# esp8266.net
KiCad netlist of a schematic drawn in EAGLE
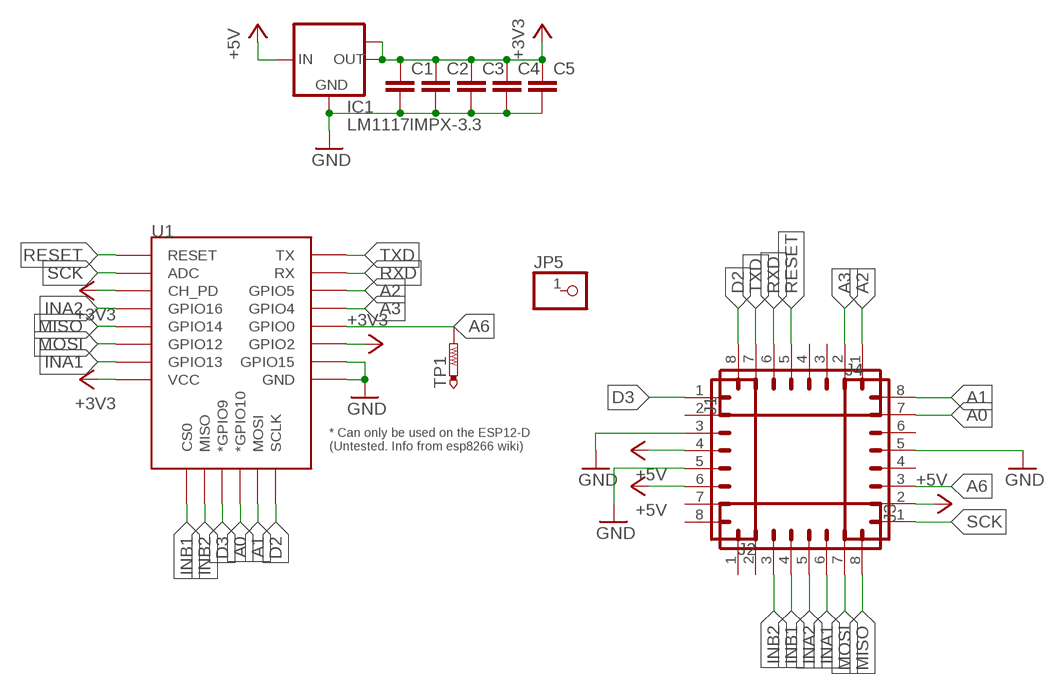
[diagram p0: schematic, sheet 1]

(export (version "E")
  (design (tool "Eeschema 10.0.6"))
  (components
    (comp (ref "C1")
      (value "C-EUC1206K")
      (footprint "eagle-import:C1206K")
      (libsource (lib "eagle-import") (part "C-EUC1206K"))
    )
    (comp (ref "C2")
      (value "C-EUC1206K")
      (footprint "eagle-import:C1206K")
      (libsource (lib "eagle-import") (part "C-EUC1206K"))
    )
    (comp (ref "C3")
      (value "C-EUC1206K")
      (footprint "eagle-import:C1206K")
      (libsource (lib "eagle-import") (part "C-EUC1206K"))
    )
    (comp (ref "C4")
      (value "C-EUC1206K")
      (footprint "eagle-import:C1206K")
      (libsource (lib "eagle-import") (part "C-EUC1206K"))
    )
    (comp (ref "C5")
      (value "C-EUC1206K")
      (footprint "eagle-import:C1206K")
      (libsource (lib "eagle-import") (part "C-EUC1206K"))
    )
    (comp (ref "IC1")
      (value "LM1117IMPX-3.3")
      (footprint "eagle-import:SOT223")
      (libsource (lib "eagle-import") (part "LM1117IMPX-3.3"))
    )
    (comp (ref "J1")
      (value "CONN_08SMD-STRAIGHT-ALT-FEMALE")
      (footprint "eagle-import:1X08_SMD_ALT")
      (libsource (lib "eagle-import") (part "CONN_08SMD-STRAIGHT-ALT-FEMALE"))
    )
    (comp (ref "J2")
      (value "CONN_08SMD-STRAIGHT-ALT-FEMALE")
      (footprint "eagle-import:1X08_SMD_ALT")
      (libsource (lib "eagle-import") (part "CONN_08SMD-STRAIGHT-ALT-FEMALE"))
    )
    (comp (ref "J3")
      (value "CONN_08SMD-STRAIGHT-ALT-FEMALE")
      (footprint "eagle-import:1X08_SMD_ALT")
      (libsource (lib "eagle-import") (part "CONN_08SMD-STRAIGHT-ALT-FEMALE"))
    )
    (comp (ref "J4")
      (value "CONN_08SMD-STRAIGHT-ALT-FEMALE")
      (footprint "eagle-import:1X08_SMD_ALT")
      (libsource (lib "eagle-import") (part "CONN_08SMD-STRAIGHT-ALT-FEMALE"))
    )
    (comp (ref "JP5")
      (value "PINHD-1X1")
      (footprint "eagle-import:1X01")
      (libsource (lib "eagle-import") (part "PINHD-1X1"))
    )
    (comp (ref "TP1")
      (value "PTR1B1,27")
      (footprint "eagle-import:B1,27")
      (libsource (lib "eagle-import") (part "PTR1B1,27"))
    )
    (comp (ref "U1")
      (value "ESP12ESMD")
      (footprint "eagle-import:ESP12E-SMD")
      (libsource (lib "eagle-import") (part "ESP12ESMD"))
    )
  )
  (nets
    (net (code "1") (name "+3V3") (class "Default")
      (node (ref "C1") (pin "1") (pinfunction "1_1") (pintype "passive"))
      (node (ref "C2") (pin "1") (pinfunction "1_1") (pintype "passive"))
      (node (ref "C3") (pin "1") (pinfunction "1_1") (pintype "passive"))
      (node (ref "C4") (pin "1") (pinfunction "1_1") (pintype "passive"))
      (node (ref "C5") (pin "1") (pinfunction "1_1") (pintype "passive"))
      (node (ref "IC1") (pin "2") (pinfunction "OUT_2") (pintype "passive"))
      (node (ref "IC1") (pin "TAB") (pinfunction "OUT1_TAB") (pintype "passive"))
      (node (ref "U1") (pin "CH_PD") (pinfunction "CH_PD_CH_PD") (pintype "bidirectional"))
      (node (ref "U1") (pin "GPIO2") (pinfunction "GPIO2_GPIO2") (pintype "bidirectional"))
      (node (ref "U1") (pin "VCC") (pinfunction "VCC_VCC") (pintype "bidirectional"))
    )
    (net (code "2") (name "+5V") (class "Default")
      (node (ref "IC1") (pin "3") (pinfunction "IN_3") (pintype "input"))
      (node (ref "J2") (pin "4") (pinfunction "4_4") (pintype "passive"))
      (node (ref "J2") (pin "6") (pinfunction "6_6") (pintype "passive"))
      (node (ref "J4") (pin "2") (pinfunction "2_2") (pintype "passive"))
    )
    (net (code "3") (name "A0") (class "Default")
      (node (ref "J4") (pin "7") (pinfunction "7_7") (pintype "passive"))
      (node (ref "U1") (pin "GPIO10") (pinfunction "*GPIO10_GPIO10") (pintype "bidirectional"))
    )
    (net (code "4") (name "A1") (class "Default")
      (node (ref "J4") (pin "8") (pinfunction "8_8") (pintype "passive"))
      (node (ref "U1") (pin "MOSI") (pinfunction "MOSI_MOSI") (pintype "bidirectional"))
    )
    (net (code "5") (name "A2") (class "Default")
      (node (ref "J1") (pin "1") (pinfunction "1_1") (pintype "passive"))
      (node (ref "U1") (pin "GPIO5") (pinfunction "GPIO5_GPIO5") (pintype "bidirectional"))
    )
    (net (code "6") (name "A3") (class "Default")
      (node (ref "J1") (pin "2") (pinfunction "2_2") (pintype "passive"))
      (node (ref "U1") (pin "GPIO4") (pinfunction "GPIO4_GPIO4") (pintype "bidirectional"))
    )
    (net (code "7") (name "A6") (class "Default")
      (node (ref "J4") (pin "3") (pinfunction "3_3") (pintype "passive"))
      (node (ref "TP1") (pin "TP") (pinfunction "TP_TP") (pintype "input"))
      (node (ref "U1") (pin "GPIO0") (pinfunction "GPIO0_GPIO0") (pintype "bidirectional"))
    )
    (net (code "8") (name "D2") (class "Default")
      (node (ref "J1") (pin "8") (pinfunction "8_8") (pintype "passive"))
      (node (ref "U1") (pin "SCLK") (pinfunction "SCLK_SCLK") (pintype "bidirectional"))
    )
    (net (code "9") (name "D3") (class "Default")
      (node (ref "J2") (pin "1") (pinfunction "1_1") (pintype "passive"))
      (node (ref "U1") (pin "GPIO9") (pinfunction "*GPIO9_GPIO9") (pintype "bidirectional"))
    )
    (net (code "10") (name "GND") (class "Default")
      (node (ref "C1") (pin "2") (pinfunction "2_2") (pintype "passive"))
      (node (ref "C2") (pin "2") (pinfunction "2_2") (pintype "passive"))
      (node (ref "C3") (pin "2") (pinfunction "2_2") (pintype "passive"))
      (node (ref "C4") (pin "2") (pinfunction "2_2") (pintype "passive"))
      (node (ref "C5") (pin "2") (pinfunction "2_2") (pintype "passive"))
      (node (ref "IC1") (pin "1") (pinfunction "GND_1") (pintype "input"))
      (node (ref "J2") (pin "3") (pinfunction "3_3") (pintype "passive"))
      (node (ref "J2") (pin "5") (pinfunction "5_5") (pintype "passive"))
      (node (ref "J4") (pin "5") (pinfunction "5_5") (pintype "passive"))
      (node (ref "U1") (pin "GND") (pinfunction "GND_GND") (pintype "bidirectional"))
      (node (ref "U1") (pin "GPIO15") (pinfunction "GPIO15_GPIO15") (pintype "bidirectional"))
    )
    (net (code "11") (name "INA1") (class "Default")
      (node (ref "J3") (pin "6") (pinfunction "6_6") (pintype "passive"))
      (node (ref "U1") (pin "GPIO13") (pinfunction "GPIO13_GPIO13") (pintype "bidirectional"))
    )
    (net (code "12") (name "INA2") (class "Default")
      (node (ref "J3") (pin "5") (pinfunction "5_5") (pintype "passive"))
      (node (ref "U1") (pin "GPIO16") (pinfunction "GPIO16_GPIO16") (pintype "bidirectional"))
    )
    (net (code "13") (name "INB1") (class "Default")
      (node (ref "J3") (pin "4") (pinfunction "4_4") (pintype "passive"))
      (node (ref "U1") (pin "CS0") (pinfunction "CS0_CS0") (pintype "bidirectional"))
    )
    (net (code "14") (name "INB2") (class "Default")
      (node (ref "J3") (pin "3") (pinfunction "3_3") (pintype "passive"))
      (node (ref "U1") (pin "MISO") (pinfunction "MISO_MISO") (pintype "bidirectional"))
    )
    (net (code "15") (name "MISO") (class "Default")
      (node (ref "J3") (pin "8") (pinfunction "8_8") (pintype "passive"))
      (node (ref "U1") (pin "GPIO14") (pinfunction "GPIO14_GPIO14") (pintype "bidirectional"))
    )
    (net (code "16") (name "MOSI") (class "Default")
      (node (ref "J3") (pin "7") (pinfunction "7_7") (pintype "passive"))
      (node (ref "U1") (pin "GPIO12") (pinfunction "GPIO12_GPIO12") (pintype "bidirectional"))
    )
    (net (code "17") (name "RESET") (class "Default")
      (node (ref "J1") (pin "5") (pinfunction "5_5") (pintype "passive"))
      (node (ref "U1") (pin "RESET") (pinfunction "RESET_RESET") (pintype "bidirectional"))
    )
    (net (code "18") (name "RXD") (class "Default")
      (node (ref "J1") (pin "6") (pinfunction "6_6") (pintype "passive"))
      (node (ref "U1") (pin "RXD0") (pinfunction "RX_RXD0") (pintype "bidirectional"))
    )
    (net (code "19") (name "SCK") (class "Default")
      (node (ref "J4") (pin "1") (pinfunction "1_1") (pintype "passive"))
      (node (ref "U1") (pin "ADC") (pinfunction "ADC_ADC") (pintype "bidirectional"))
    )
    (net (code "20") (name "TXD") (class "Default")
      (node (ref "J1") (pin "7") (pinfunction "7_7") (pintype "passive"))
      (node (ref "U1") (pin "TXD0") (pinfunction "TX_TXD0") (pintype "bidirectional"))
    )
    (net (code "21") (name "unconnected-(J1-Pad3)") (class "Default")
      (node (ref "J1") (pin "3") (pinfunction "3_3") (pintype "passive"))
    )
    (net (code "22") (name "unconnected-(J1-Pad4)") (class "Default")
      (node (ref "J1") (pin "4") (pinfunction "4_4") (pintype "passive"))
    )
    (net (code "23") (name "unconnected-(J2-Pad2)") (class "Default")
      (node (ref "J2") (pin "2") (pinfunction "2_2") (pintype "passive"))
    )
    (net (code "24") (name "unconnected-(J2-Pad7)") (class "Default")
      (node (ref "J2") (pin "7") (pinfunction "7_7") (pintype "passive"))
    )
    (net (code "25") (name "unconnected-(J2-Pad8)") (class "Default")
      (node (ref "J2") (pin "8") (pinfunction "8_8") (pintype "passive"))
    )
    (net (code "26") (name "unconnected-(J3-Pad1)") (class "Default")
      (node (ref "J3") (pin "1") (pinfunction "1_1") (pintype "passive"))
    )
    (net (code "27") (name "unconnected-(J3-Pad2)") (class "Default")
      (node (ref "J3") (pin "2") (pinfunction "2_2") (pintype "passive"))
    )
    (net (code "28") (name "unconnected-(J4-Pad4)") (class "Default")
      (node (ref "J4") (pin "4") (pinfunction "4_4") (pintype "passive"))
    )
    (net (code "29") (name "unconnected-(J4-Pad6)") (class "Default")
      (node (ref "J4") (pin "6") (pinfunction "6_6") (pintype "passive"))
    )
    (net (code "30") (name "unconnected-(JP5-Pad1)") (class "Default")
      (node (ref "JP5") (pin "1") (pinfunction "1_1") (pintype "passive"))
    )
  )
)
